# OutControl.net
KiCad netlist of a schematic drawn in Altium Designer
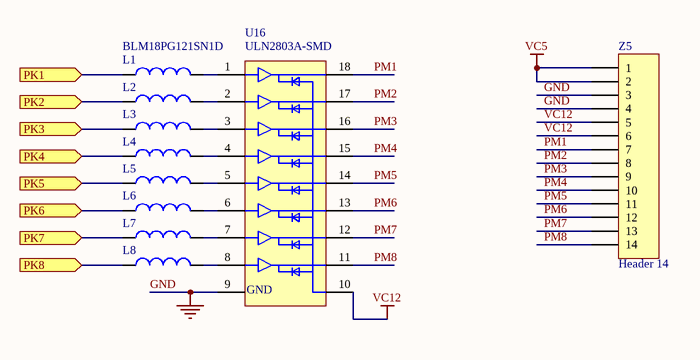
[diagram p0: OutControl.SchDoc]

(export (version "E")
  (design (tool "Eeschema 10.0.6"))
  (components
    (comp (ref "L1")
      (value "BLM18PG121SN1D")
      (footprint "0603L")
      (description "Bead,120R,2A,0603,BLM18PG121SN1D,MURATA")
      (libsource (lib "MCD_TOOLS") (part "BEAD_120R_2A_0603"))
    )
    (comp (ref "L2")
      (value "BLM18PG121SN1D")
      (footprint "0603L")
      (description "Bead,120R,2A,0603,BLM18PG121SN1D,MURATA")
      (libsource (lib "MCD_TOOLS") (part "BEAD_120R_2A_0603"))
    )
    (comp (ref "L3")
      (value "BLM18PG121SN1D")
      (footprint "0603L")
      (description "Bead,120R,2A,0603,BLM18PG121SN1D,MURATA")
      (libsource (lib "MCD_TOOLS") (part "BEAD_120R_2A_0603"))
    )
    (comp (ref "L4")
      (value "BLM18PG121SN1D")
      (footprint "0603L")
      (description "Bead,120R,2A,0603,BLM18PG121SN1D,MURATA")
      (libsource (lib "MCD_TOOLS") (part "BEAD_120R_2A_0603"))
    )
    (comp (ref "L5")
      (value "BLM18PG121SN1D")
      (footprint "0603L")
      (description "Bead,120R,2A,0603,BLM18PG121SN1D,MURATA")
      (libsource (lib "MCD_TOOLS") (part "BEAD_120R_2A_0603"))
    )
    (comp (ref "L6")
      (value "BLM18PG121SN1D")
      (footprint "0603L")
      (description "Bead,120R,2A,0603,BLM18PG121SN1D,MURATA")
      (libsource (lib "MCD_TOOLS") (part "BEAD_120R_2A_0603"))
    )
    (comp (ref "L7")
      (value "BLM18PG121SN1D")
      (footprint "0603L")
      (description "Bead,120R,2A,0603,BLM18PG121SN1D,MURATA")
      (libsource (lib "MCD_TOOLS") (part "BEAD_120R_2A_0603"))
    )
    (comp (ref "L8")
      (value "BLM18PG121SN1D")
      (footprint "0603L")
      (description "Bead,120R,2A,0603,BLM18PG121SN1D,MURATA")
      (libsource (lib "MCD_TOOLS") (part "BEAD_120R_2A_0603"))
    )
    (comp (ref "U16") (value "ULN2803A-SMD") (footprint "SOL18") (libsource (lib "*") (part "ULN2803")))
    (comp (ref "Z5")
      (value "Header 14")
      (footprint "UMATCH-14")
      (description "Header, 14-Pin")
      (fields (field (name "PUBLISHER") "Altium Limited"))
      (libsource (lib "Miscellaneous Connectors") (part "Header 14"))
    )
  )
  (nets
    (net (code "1") (name "/PK1") (class "Default")
      (node (ref "L1") (pin "1") (pinfunction "1_1") (pintype "passive"))
    )
    (net (code "2") (name "/PK2") (class "Default")
      (node (ref "L2") (pin "1") (pinfunction "1_1") (pintype "passive"))
    )
    (net (code "3") (name "/PK3") (class "Default")
      (node (ref "L3") (pin "1") (pinfunction "1_1") (pintype "passive"))
    )
    (net (code "4") (name "/PK4") (class "Default")
      (node (ref "L4") (pin "1") (pinfunction "1_1") (pintype "passive"))
    )
    (net (code "5") (name "/PK5") (class "Default")
      (node (ref "L5") (pin "1") (pinfunction "1_1") (pintype "passive"))
    )
    (net (code "6") (name "/PK6") (class "Default")
      (node (ref "L6") (pin "1") (pinfunction "1_1") (pintype "passive"))
    )
    (net (code "7") (name "/PK7") (class "Default")
      (node (ref "L7") (pin "1") (pinfunction "1_1") (pintype "passive"))
    )
    (net (code "8") (name "/PK8") (class "Default")
      (node (ref "L8") (pin "1") (pinfunction "1_1") (pintype "passive"))
    )
    (net (code "9") (name "/PM1") (class "Default")
      (node (ref "U16") (pin "18") (pintype "passive"))
      (node (ref "Z5") (pin "7") (pinfunction "7_7") (pintype "passive"))
    )
    (net (code "10") (name "/PM2") (class "Default")
      (node (ref "U16") (pin "17") (pintype "passive"))
      (node (ref "Z5") (pin "8") (pinfunction "8_8") (pintype "passive"))
    )
    (net (code "11") (name "/PM3") (class "Default")
      (node (ref "U16") (pin "16") (pintype "passive"))
      (node (ref "Z5") (pin "9") (pinfunction "9_9") (pintype "passive"))
    )
    (net (code "12") (name "/PM4") (class "Default")
      (node (ref "U16") (pin "15") (pintype "passive"))
      (node (ref "Z5") (pin "10") (pinfunction "10_10") (pintype "passive"))
    )
    (net (code "13") (name "/PM5") (class "Default")
      (node (ref "U16") (pin "14") (pintype "passive"))
      (node (ref "Z5") (pin "11") (pinfunction "11_11") (pintype "passive"))
    )
    (net (code "14") (name "/PM6") (class "Default")
      (node (ref "U16") (pin "13") (pintype "passive"))
      (node (ref "Z5") (pin "12") (pinfunction "12_12") (pintype "passive"))
    )
    (net (code "15") (name "/PM7") (class "Default")
      (node (ref "U16") (pin "12") (pintype "passive"))
      (node (ref "Z5") (pin "13") (pinfunction "13_13") (pintype "passive"))
    )
    (net (code "16") (name "/PM8") (class "Default")
      (node (ref "U16") (pin "11") (pintype "passive"))
      (node (ref "Z5") (pin "14") (pinfunction "14_14") (pintype "passive"))
    )
    (net (code "17") (name "GND") (class "Default")
      (node (ref "U16") (pin "9") (pintype "passive"))
      (node (ref "Z5") (pin "3") (pinfunction "3_3") (pintype "passive"))
      (node (ref "Z5") (pin "4") (pinfunction "4_4") (pintype "passive"))
    )
    (net (code "18") (name "Net-(L1-Pad2)") (class "Default")
      (node (ref "L1") (pin "2") (pinfunction "2_2") (pintype "passive"))
      (node (ref "U16") (pin "1") (pintype "passive"))
    )
    (net (code "19") (name "Net-(L2-Pad2)") (class "Default")
      (node (ref "L2") (pin "2") (pinfunction "2_2") (pintype "passive"))
      (node (ref "U16") (pin "2") (pintype "passive"))
    )
    (net (code "20") (name "Net-(L3-Pad2)") (class "Default")
      (node (ref "L3") (pin "2") (pinfunction "2_2") (pintype "passive"))
      (node (ref "U16") (pin "3") (pintype "passive"))
    )
    (net (code "21") (name "Net-(L4-Pad2)") (class "Default")
      (node (ref "L4") (pin "2") (pinfunction "2_2") (pintype "passive"))
      (node (ref "U16") (pin "4") (pintype "passive"))
    )
    (net (code "22") (name "Net-(L5-Pad2)") (class "Default")
      (node (ref "L5") (pin "2") (pinfunction "2_2") (pintype "passive"))
      (node (ref "U16") (pin "5") (pintype "passive"))
    )
    (net (code "23") (name "Net-(L6-Pad2)") (class "Default")
      (node (ref "L6") (pin "2") (pinfunction "2_2") (pintype "passive"))
      (node (ref "U16") (pin "6") (pintype "passive"))
    )
    (net (code "24") (name "Net-(L7-Pad2)") (class "Default")
      (node (ref "L7") (pin "2") (pinfunction "2_2") (pintype "passive"))
      (node (ref "U16") (pin "7") (pintype "passive"))
    )
    (net (code "25") (name "Net-(L8-Pad2)") (class "Default")
      (node (ref "L8") (pin "2") (pinfunction "2_2") (pintype "passive"))
      (node (ref "U16") (pin "8") (pintype "passive"))
    )
    (net (code "26") (name "VC5") (class "Default")
      (node (ref "Z5") (pin "1") (pinfunction "1_1") (pintype "passive"))
      (node (ref "Z5") (pin "2") (pinfunction "2_2") (pintype "passive"))
    )
    (net (code "27") (name "VC12") (class "Default")
      (node (ref "U16") (pin "10") (pintype "passive"))
      (node (ref "Z5") (pin "5") (pinfunction "5_5") (pintype "passive"))
      (node (ref "Z5") (pin "6") (pinfunction "6_6") (pintype "passive"))
    )
  )
)
